# AccelAdapter.net
KiCad netlist of a schematic drawn in EAGLE
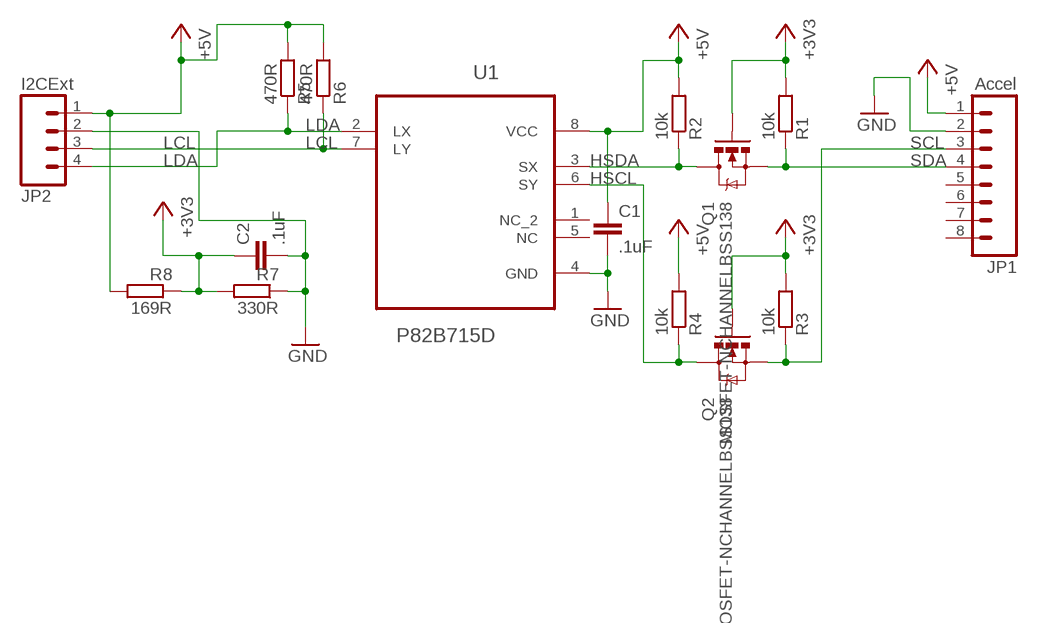
[diagram p0: schematic, sheet 1]

(export (version "E")
  (design (tool "Eeschema 10.0.6"))
  (components
    (comp (ref "C1")
      (value ".1uF")
      (footprint "eagle-import:C0805")
      (fields (field (name "MPN") "MCCA000386"))
      (libsource (lib "eagle-import") (part "C-EUC0805"))
    )
    (comp (ref "C2")
      (value ".1uF")
      (footprint "eagle-import:C0805")
      (fields (field (name "MPN") "MCCA000386"))
      (libsource (lib "eagle-import") (part "C-EUC0805"))
    )
    (comp (ref "JP1")
      (value "Accel")
      (footprint "eagle-import:1X08")
      (libsource (lib "eagle-import") (part "M081X08"))
    )
    (comp (ref "JP2")
      (value "I2CExt")
      (footprint "eagle-import:1X04")
      (libsource (lib "eagle-import") (part "M04PTH"))
    )
    (comp (ref "Q1")
      (value "MOSFET-NCHANNELBSS138")
      (footprint "eagle-import:SOT23")
      (libsource (lib "eagle-import") (part "MOSFET-NCHANNELBSS138"))
    )
    (comp (ref "Q2")
      (value "MOSFET-NCHANNELBSS138")
      (footprint "eagle-import:SOT23")
      (libsource (lib "eagle-import") (part "MOSFET-NCHANNELBSS138"))
    )
    (comp (ref "R1")
      (value "10k")
      (footprint "eagle-import:R0805")
      (fields (field (name "MPN") "RC0805JR-1310KL"))
      (libsource (lib "eagle-import") (part "R-EU_R0805"))
    )
    (comp (ref "R2")
      (value "10k")
      (footprint "eagle-import:R0805")
      (fields (field (name "MPN") "RC0805JR-1310KL"))
      (libsource (lib "eagle-import") (part "R-EU_R0805"))
    )
    (comp (ref "R3")
      (value "10k")
      (footprint "eagle-import:R0805")
      (fields (field (name "MPN") "RC0805JR-1310KL"))
      (libsource (lib "eagle-import") (part "R-EU_R0805"))
    )
    (comp (ref "R4")
      (value "10k")
      (footprint "eagle-import:R0805")
      (fields (field (name "MPN") "RC0805JR-1310KL"))
      (libsource (lib "eagle-import") (part "R-EU_R0805"))
    )
    (comp (ref "R5")
      (value "470R")
      (footprint "eagle-import:R0805")
      (fields (field (name "MPN") "RC0805JR-07470RL"))
      (libsource (lib "eagle-import") (part "R-EU_R0805"))
    )
    (comp (ref "R6")
      (value "470R")
      (footprint "eagle-import:R0805")
      (fields (field (name "MPN") "RC0805JR-07470RL"))
      (libsource (lib "eagle-import") (part "R-EU_R0805"))
    )
    (comp (ref "R7")
      (value "330R")
      (footprint "eagle-import:R0805")
      (fields (field (name "MPN") "RC0805JR-07470RL"))
      (libsource (lib "eagle-import") (part "R-EU_R0805"))
    )
    (comp (ref "R8")
      (value "169R")
      (footprint "eagle-import:R0805")
      (fields (field (name "MPN") "RC0805JR-07470RL"))
      (libsource (lib "eagle-import") (part "R-EU_R0805"))
    )
    (comp (ref "U1")
      (value "P82B715D")
      (footprint "eagle-import:SOIC127P600X175-8N")
      (libsource (lib "eagle-import") (part "P82B715D"))
    )
  )
  (nets
    (net (code "1") (name "+3V3") (class "Default")
      (node (ref "C2") (pin "1") (pinfunction "1_1") (pintype "passive"))
      (node (ref "Q1") (pin "1") (pinfunction "G_1") (pintype "passive"))
      (node (ref "Q2") (pin "1") (pinfunction "G_1") (pintype "passive"))
      (node (ref "R1") (pin "2") (pinfunction "2_2") (pintype "passive"))
      (node (ref "R3") (pin "2") (pinfunction "2_2") (pintype "passive"))
      (node (ref "R7") (pin "2") (pinfunction "2_2") (pintype "passive"))
      (node (ref "R8") (pin "1") (pinfunction "1_1") (pintype "passive"))
    )
    (net (code "2") (name "+5V") (class "Default")
      (node (ref "C1") (pin "1") (pinfunction "1_1") (pintype "passive"))
      (node (ref "JP1") (pin "1") (pinfunction "1_1") (pintype "passive"))
      (node (ref "JP2") (pin "1") (pinfunction "1_1") (pintype "passive"))
      (node (ref "R2") (pin "2") (pinfunction "2_2") (pintype "passive"))
      (node (ref "R4") (pin "2") (pinfunction "2_2") (pintype "passive"))
      (node (ref "R5") (pin "2") (pinfunction "2_2") (pintype "passive"))
      (node (ref "R6") (pin "2") (pinfunction "2_2") (pintype "passive"))
      (node (ref "R8") (pin "2") (pinfunction "2_2") (pintype "passive"))
      (node (ref "U1") (pin "8") (pinfunction "VCC_8") (pintype "power_in"))
    )
    (net (code "3") (name "/HSCL") (class "Default")
      (node (ref "Q2") (pin "3") (pinfunction "D_3") (pintype "passive"))
      (node (ref "R4") (pin "1") (pinfunction "1_1") (pintype "passive"))
      (node (ref "U1") (pin "6") (pinfunction "SY_6") (pintype "input"))
    )
    (net (code "4") (name "/HSDA") (class "Default")
      (node (ref "Q1") (pin "3") (pinfunction "D_3") (pintype "passive"))
      (node (ref "R2") (pin "1") (pinfunction "1_1") (pintype "passive"))
      (node (ref "U1") (pin "3") (pinfunction "SX_3") (pintype "input"))
    )
    (net (code "5") (name "/LCL") (class "Default")
      (node (ref "JP2") (pin "3") (pinfunction "3_3") (pintype "passive"))
      (node (ref "R6") (pin "1") (pinfunction "1_1") (pintype "passive"))
      (node (ref "U1") (pin "7") (pinfunction "LY_7") (pintype "output"))
    )
    (net (code "6") (name "/LDA") (class "Default")
      (node (ref "JP2") (pin "4") (pinfunction "4_4") (pintype "passive"))
      (node (ref "R5") (pin "1") (pinfunction "1_1") (pintype "passive"))
      (node (ref "U1") (pin "2") (pinfunction "LX_2") (pintype "output"))
    )
    (net (code "7") (name "/SCL") (class "Default")
      (node (ref "JP1") (pin "3") (pinfunction "3_3") (pintype "passive"))
      (node (ref "Q2") (pin "2") (pinfunction "S_2") (pintype "passive"))
      (node (ref "R3") (pin "1") (pinfunction "1_1") (pintype "passive"))
    )
    (net (code "8") (name "/SDA") (class "Default")
      (node (ref "JP1") (pin "4") (pinfunction "4_4") (pintype "passive"))
      (node (ref "Q1") (pin "2") (pinfunction "S_2") (pintype "passive"))
      (node (ref "R1") (pin "1") (pinfunction "1_1") (pintype "passive"))
    )
    (net (code "9") (name "GND") (class "Default")
      (node (ref "C1") (pin "2") (pinfunction "2_2") (pintype "passive"))
      (node (ref "C2") (pin "2") (pinfunction "2_2") (pintype "passive"))
      (node (ref "JP1") (pin "2") (pinfunction "2_2") (pintype "passive"))
      (node (ref "JP2") (pin "2") (pinfunction "2_2") (pintype "passive"))
      (node (ref "R7") (pin "1") (pinfunction "1_1") (pintype "passive"))
      (node (ref "U1") (pin "4") (pinfunction "GND_4") (pintype "passive"))
    )
    (net (code "10") (name "unconnected-(JP1-Pad5)") (class "Default")
      (node (ref "JP1") (pin "5") (pinfunction "5_5") (pintype "passive"))
    )
    (net (code "11") (name "unconnected-(JP1-Pad6)") (class "Default")
      (node (ref "JP1") (pin "6") (pinfunction "6_6") (pintype "passive"))
    )
    (net (code "12") (name "unconnected-(JP1-Pad7)") (class "Default")
      (node (ref "JP1") (pin "7") (pinfunction "7_7") (pintype "passive"))
    )
    (net (code "13") (name "unconnected-(JP1-Pad8)") (class "Default")
      (node (ref "JP1") (pin "8") (pinfunction "8_8") (pintype "passive"))
    )
    (net (code "14") (name "unconnected-(U1-NC-Pad5)") (class "Default")
      (node (ref "U1") (pin "5") (pinfunction "NC_5") (pintype "no_connect"))
    )
    (net (code "15") (name "unconnected-(U1-NC_2-Pad1)") (class "Default")
      (node (ref "U1") (pin "1") (pinfunction "NC_2_1") (pintype "no_connect"))
    )
  )
)
